# CPU.net
KiCad netlist of a schematic drawn in Altium Designer
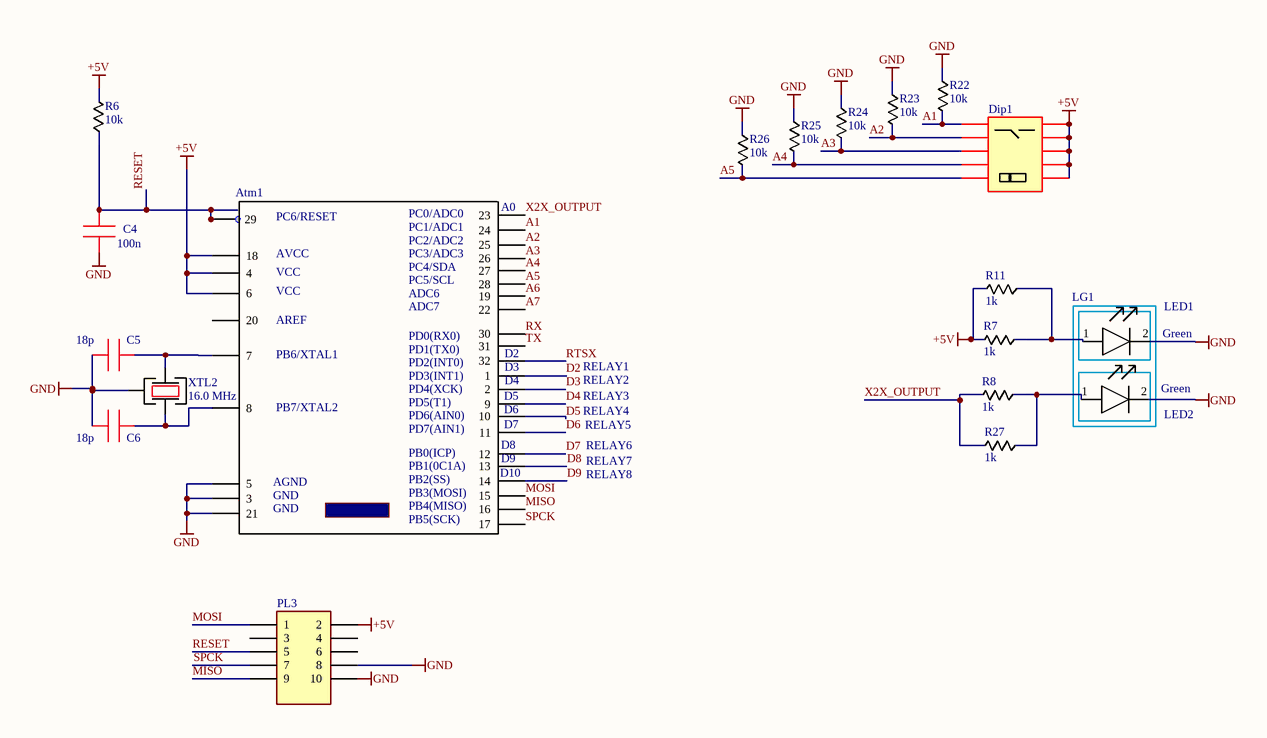
[diagram p0: CPU.SchDoc]

(export (version "E")
  (design (tool "Eeschema 10.0.6"))
  (components
    (comp (ref "Atm1")
      (value "~")
      (footprint "Atmega168")
      (fields (field (name "PART NUMBER") "Atmega328P-AU"))
      (libsource (lib "kontr") (part "Atmega328"))
    )
    (comp (ref "C4")
      (value "100n")
      (footprint "0603_Cap")
      (fields (field (name "PART NUMBER") "CC0603ZRY5V9BB104"))
      (libsource (lib "kontr") (part "Capasitor 0805"))
    )
    (comp (ref "C5")
      (value "18p")
      (footprint "0603_Cap")
      (fields (field (name "PART NUMBER") "CC0603JRNPO9BN180"))
      (libsource (lib "kontr") (part "Capasitor 0805"))
    )
    (comp (ref "C6")
      (value "18p")
      (footprint "0603_Cap")
      (fields (field (name "PART NUMBER") "CC0603JRNPO9BN180"))
      (libsource (lib "kontr") (part "Capasitor 0805"))
    )
    (comp (ref "Dip1")
      (value "~")
      (footprint "DipSwitch 5")
      (fields (field (name "PART NUMBER") "DPL-05-V"))
      (libsource (lib "kontr") (part "DipSwitch5"))
    )
    (comp (ref "LED1")
      (value "~")
      (footprint "0603 - LED")
      (fields (field (name "PART NUMBER") "KP-1608SGC"))
      (libsource (lib "МЦТР.00010572.00.001") (part "LED 0603"))
    )
    (comp (ref "LED2")
      (value "~")
      (footprint "0603 - LED")
      (fields (field (name "PART NUMBER") "KP-1608SGC"))
      (libsource (lib "МЦТР.00010572.00.001") (part "LED 0603"))
    )
    (comp (ref "LG1")
      (value "~")
      (footprint "LED SMD DayLight")
      (fields (field (name "PART NUMBER") "5151094F"))
      (libsource (lib "МЦТР.00010572.00.001") (part "Light Guide 2"))
    )
    (comp (ref "PL3")
      (value "~")
      (footprint "IDC-10MS")
      (fields (field (name "PART NUMBER") "DS1013-10SSIB1-B-0"))
      (libsource (lib "kontr") (part "IDC-10MS"))
    )
    (comp (ref "R6")
      (value "10k")
      (footprint "0603_Res")
      (fields (field (name "PART NUMBER") "RT0603FRE0710KL"))
      (libsource (lib "kontr") (part "Resistor 0805"))
    )
    (comp (ref "R7")
      (value "1k")
      (footprint "0603_Res")
      (fields (field (name "PART NUMBER") "RC0603FR-071KL"))
      (libsource (lib "kontr") (part "Resistor 0805"))
    )
    (comp (ref "R8")
      (value "1k")
      (footprint "0603_Res")
      (fields (field (name "PART NUMBER") "RC0603FR-071KL"))
      (libsource (lib "kontr") (part "Resistor 0805"))
    )
    (comp (ref "R11")
      (value "1k")
      (footprint "0603_Res")
      (fields (field (name "PART NUMBER") "RC0603FR-071KL"))
      (libsource (lib "kontr") (part "Resistor 0805"))
    )
    (comp (ref "R22")
      (value "10k")
      (footprint "0603_Res")
      (fields (field (name "PART NUMBER") "RT0603FRE0710KL"))
      (libsource (lib "kontr") (part "Resistor 0805"))
    )
    (comp (ref "R23")
      (value "10k")
      (footprint "0603_Res")
      (fields (field (name "PART NUMBER") "RT0603FRE0710KL"))
      (libsource (lib "kontr") (part "Resistor 0805"))
    )
    (comp (ref "R24")
      (value "10k")
      (footprint "0603_Res")
      (fields (field (name "PART NUMBER") "RT0603FRE0710KL"))
      (libsource (lib "kontr") (part "Resistor 0805"))
    )
    (comp (ref "R25")
      (value "10k")
      (footprint "0603_Res")
      (fields (field (name "PART NUMBER") "RT0603FRE0710KL"))
      (libsource (lib "kontr") (part "Resistor 0805"))
    )
    (comp (ref "R26")
      (value "10k")
      (footprint "0603_Res")
      (fields (field (name "PART NUMBER") "RT0603FRE0710KL"))
      (libsource (lib "kontr") (part "Resistor 0805"))
    )
    (comp (ref "R27")
      (value "1k")
      (footprint "0603_Res")
      (fields (field (name "PART NUMBER") "RC0603FR-071KL"))
      (libsource (lib "kontr") (part "Resistor 0805"))
    )
    (comp (ref "XTL2")
      (value "16.0 MHz")
      (footprint "KX-7 XTAL")
      (fields (field (name "PART NUMBER") "Geyer KX-7 16.0 MHz"))
      (libsource (lib "kontr") (part "KX-7"))
    )
  )
  (nets
    (net (code "1") (name "+5V") (class "Default")
      (node (ref "Atm1") (pin "18") (pinfunction "18_18") (pintype "passive"))
      (node (ref "Atm1") (pin "4") (pinfunction "4_4") (pintype "passive"))
      (node (ref "Atm1") (pin "6") (pinfunction "6_6") (pintype "passive"))
      (node (ref "Dip1") (pin "1") (pinfunction "1_1") (pintype "passive"))
      (node (ref "Dip1") (pin "2") (pinfunction "3_2") (pintype "passive"))
      (node (ref "Dip1") (pin "3") (pinfunction "5_3") (pintype "passive"))
      (node (ref "Dip1") (pin "4") (pinfunction "7_4") (pintype "passive"))
      (node (ref "Dip1") (pin "5") (pinfunction "9_5") (pintype "passive"))
      (node (ref "PL3") (pin "2") (pinfunction "2_2") (pintype "passive"))
      (node (ref "R11") (pin "2") (pintype "passive"))
      (node (ref "R6") (pin "2") (pintype "passive"))
      (node (ref "R7") (pin "2") (pintype "passive"))
    )
    (net (code "2") (name "/A1") (class "Default")
      (node (ref "Atm1") (pin "24") (pinfunction "24_24") (pintype "passive"))
      (node (ref "Dip1") (pin "12") (pinfunction "10_12") (pintype "passive"))
      (node (ref "R22") (pin "2") (pintype "passive"))
    )
    (net (code "3") (name "/A2") (class "Default")
      (node (ref "Atm1") (pin "25") (pinfunction "25_25") (pintype "passive"))
      (node (ref "Dip1") (pin "13") (pinfunction "8_13") (pintype "passive"))
      (node (ref "R23") (pin "2") (pintype "passive"))
    )
    (net (code "4") (name "/A3") (class "Default")
      (node (ref "Atm1") (pin "26") (pinfunction "26_26") (pintype "passive"))
      (node (ref "Dip1") (pin "14") (pinfunction "6_14") (pintype "passive"))
      (node (ref "R24") (pin "2") (pintype "passive"))
    )
    (net (code "5") (name "/A4") (class "Default")
      (node (ref "Atm1") (pin "27") (pinfunction "27_27") (pintype "passive"))
      (node (ref "Dip1") (pin "15") (pinfunction "4_15") (pintype "passive"))
      (node (ref "R25") (pin "2") (pintype "passive"))
    )
    (net (code "6") (name "/A5") (class "Default")
      (node (ref "Atm1") (pin "28") (pinfunction "28_28") (pintype "passive"))
      (node (ref "Dip1") (pin "16") (pinfunction "2_16") (pintype "passive"))
      (node (ref "R26") (pin "2") (pintype "passive"))
    )
    (net (code "7") (name "/A6") (class "Default")
      (node (ref "Atm1") (pin "19") (pinfunction "19_19") (pintype "passive"))
    )
    (net (code "8") (name "/A7") (class "Default")
      (node (ref "Atm1") (pin "22") (pinfunction "22_22") (pintype "passive"))
    )
    (net (code "9") (name "/D2") (class "Default")
      (node (ref "Atm1") (pin "1") (pinfunction "1_1") (pintype "passive"))
    )
    (net (code "10") (name "/D3") (class "Default")
      (node (ref "Atm1") (pin "2") (pinfunction "2_2") (pintype "passive"))
    )
    (net (code "11") (name "/D4") (class "Default")
      (node (ref "Atm1") (pin "9") (pinfunction "9_9") (pintype "passive"))
    )
    (net (code "12") (name "/D5") (class "Default")
      (node (ref "Atm1") (pin "10") (pinfunction "10_10") (pintype "passive"))
    )
    (net (code "13") (name "/D6") (class "Default")
      (node (ref "Atm1") (pin "11") (pinfunction "11_11") (pintype "passive"))
    )
    (net (code "14") (name "/D7") (class "Default")
      (node (ref "Atm1") (pin "12") (pinfunction "12_12") (pintype "passive"))
    )
    (net (code "15") (name "/D8") (class "Default")
      (node (ref "Atm1") (pin "13") (pinfunction "13_13") (pintype "passive"))
    )
    (net (code "16") (name "/D9") (class "Default")
      (node (ref "Atm1") (pin "14") (pinfunction "14_14") (pintype "passive"))
    )
    (net (code "17") (name "/MISO") (class "Default")
      (node (ref "Atm1") (pin "16") (pinfunction "16_16") (pintype "passive"))
      (node (ref "PL3") (pin "9") (pinfunction "9_9") (pintype "passive"))
    )
    (net (code "18") (name "/MOSI") (class "Default")
      (node (ref "Atm1") (pin "15") (pinfunction "15_15") (pintype "passive"))
      (node (ref "PL3") (pin "1") (pinfunction "1_1") (pintype "passive"))
    )
    (net (code "19") (name "/RESET") (class "Default")
      (node (ref "Atm1") (pin "29") (pinfunction "29_29") (pintype "passive"))
      (node (ref "C4") (pin "2") (pinfunction "2_2") (pintype "passive"))
      (node (ref "PL3") (pin "5") (pinfunction "5_5") (pintype "passive"))
      (node (ref "R6") (pin "1") (pintype "passive"))
    )
    (net (code "20") (name "/RTSX") (class "Default")
      (node (ref "Atm1") (pin "32") (pinfunction "32_32") (pintype "passive"))
    )
    (net (code "21") (name "/RX") (class "Default")
      (node (ref "Atm1") (pin "30") (pinfunction "30_30") (pintype "passive"))
    )
    (net (code "22") (name "/SPCK") (class "Default")
      (node (ref "Atm1") (pin "17") (pinfunction "17_17") (pintype "passive"))
      (node (ref "PL3") (pin "7") (pinfunction "7_7") (pintype "passive"))
    )
    (net (code "23") (name "/TX") (class "Default")
      (node (ref "Atm1") (pin "31") (pinfunction "31_31") (pintype "passive"))
    )
    (net (code "24") (name "/X2X_OUTPUT") (class "Default")
      (node (ref "Atm1") (pin "23") (pinfunction "23_23") (pintype "passive"))
      (node (ref "R27") (pin "2") (pintype "passive"))
      (node (ref "R8") (pin "2") (pintype "passive"))
    )
    (net (code "25") (name "GND") (class "Default")
      (node (ref "Atm1") (pin "21") (pinfunction "21_21") (pintype "passive"))
      (node (ref "Atm1") (pin "3") (pinfunction "3_3") (pintype "passive"))
      (node (ref "Atm1") (pin "5") (pinfunction "5_5") (pintype "passive"))
      (node (ref "C4") (pin "1") (pinfunction "1_1") (pintype "passive"))
      (node (ref "C5") (pin "1") (pinfunction "1_1") (pintype "passive"))
      (node (ref "C6") (pin "1") (pinfunction "1_1") (pintype "passive"))
      (node (ref "LED1") (pin "2") (pintype "passive"))
      (node (ref "LED2") (pin "2") (pintype "passive"))
      (node (ref "PL3") (pin "10") (pinfunction "10_10") (pintype "passive"))
      (node (ref "PL3") (pin "8") (pinfunction "8_8") (pintype "passive"))
      (node (ref "R22") (pin "1") (pintype "passive"))
      (node (ref "R23") (pin "1") (pintype "passive"))
      (node (ref "R24") (pin "1") (pintype "passive"))
      (node (ref "R25") (pin "1") (pintype "passive"))
      (node (ref "R26") (pin "1") (pintype "passive"))
      (node (ref "XTL2") (pin "2") (pinfunction "2_2") (pintype "passive"))
    )
    (net (code "26") (name "Net-(Atm1-Pad7)") (class "Default")
      (node (ref "Atm1") (pin "7") (pinfunction "7_7") (pintype "passive"))
      (node (ref "C5") (pin "2") (pinfunction "2_2") (pintype "passive"))
      (node (ref "XTL2") (pin "1") (pinfunction "5_1") (pintype "passive"))
    )
    (net (code "27") (name "Net-(Atm1-Pad8)") (class "Default")
      (node (ref "Atm1") (pin "8") (pinfunction "8_8") (pintype "passive"))
      (node (ref "C6") (pin "2") (pinfunction "2_2") (pintype "passive"))
      (node (ref "XTL2") (pin "3") (pinfunction "5_3") (pintype "passive"))
    )
    (net (code "28") (name "Net-(LED1-Pad1)") (class "Default")
      (node (ref "LED1") (pin "1") (pintype "passive"))
      (node (ref "R11") (pin "1") (pintype "passive"))
      (node (ref "R7") (pin "1") (pintype "passive"))
    )
    (net (code "29") (name "Net-(LED2-Pad1)") (class "Default")
      (node (ref "LED2") (pin "1") (pintype "passive"))
      (node (ref "R27") (pin "1") (pintype "passive"))
      (node (ref "R8") (pin "1") (pintype "passive"))
    )
    (net (code "30") (name "unconnected-(Atm1-Pad20)") (class "Default")
      (node (ref "Atm1") (pin "20") (pinfunction "20_20") (pintype "passive"))
    )
    (net (code "31") (name "unconnected-(PL3-Pad3)") (class "Default")
      (node (ref "PL3") (pin "3") (pinfunction "3_3") (pintype "passive"))
    )
    (net (code "32") (name "unconnected-(PL3-Pad4)") (class "Default")
      (node (ref "PL3") (pin "4") (pinfunction "4_4") (pintype "passive"))
    )
    (net (code "33") (name "unconnected-(PL3-Pad6)") (class "Default")
      (node (ref "PL3") (pin "6") (pinfunction "6_6") (pintype "passive"))
    )
  )
)
